# LM61495Q3_PINOUT.net
KiCad netlist of a schematic drawn in Altium Designer
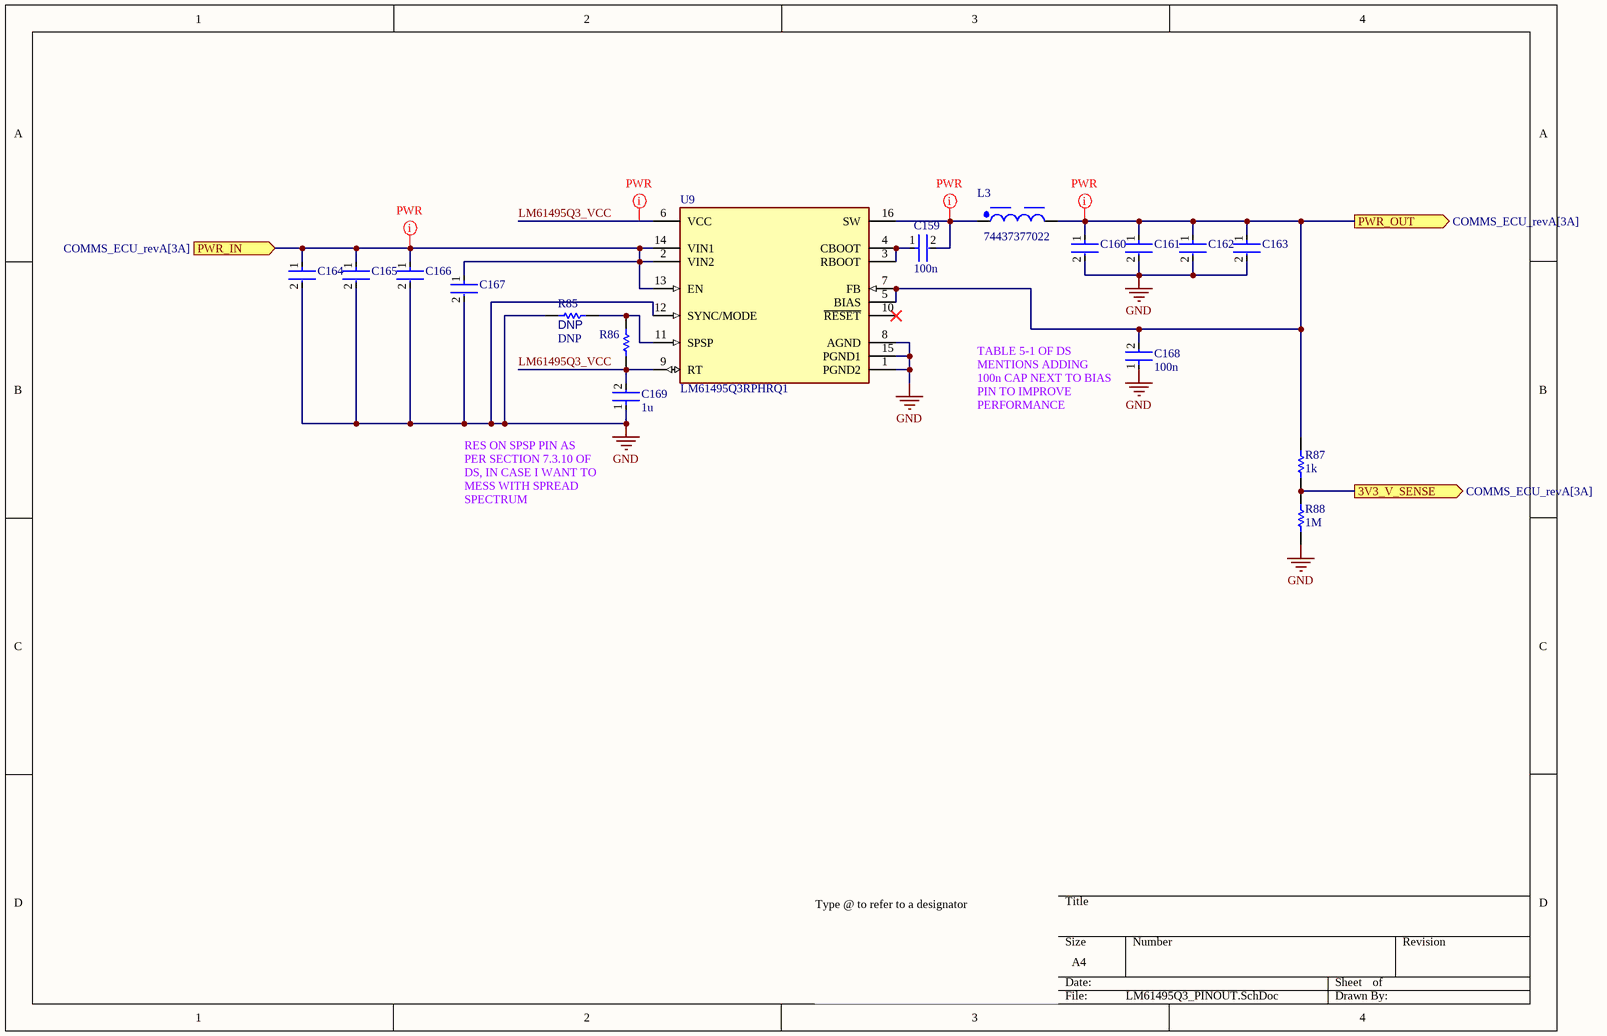
[diagram p0: LM61495Q3_PINOUT.SchDoc]

(export (version "E")
  (design (tool "Eeschema 10.0.6"))
  (components
    (comp (ref "C159")
      (value "100n")
      (footprint "FP-0402-L_1_0_0_05-W_0_5-IPC_A")
      (description "LARGE PADS, 0402 CAP, CHANGE COMMENT TO MATCH REAL P/N")
      (libsource (lib "Space Concordia") (part "b4654b650e69147ec39a6b967a45e02"))
    )
    (comp (ref "C160")
      (value "GRM32ER61C476KE15L")
      (footprint "FP-GRM32E-0_3-0_2-IPC_C")
      (description "CAP CER 47UF 16V X5R 1210")
      (fields (field (name "VOLTAGE") "16V") (field (name "TOLERANCE") "10%"))
      (libsource (lib "Altium Content Vault") (part "b4654b650e69147ec39a6b967a45e02"))
    )
    (comp (ref "C161")
      (value "GRM32ER61C476KE15L")
      (footprint "FP-GRM32E-0_3-0_2-IPC_C")
      (description "CAP CER 47UF 16V X5R 1210")
      (fields (field (name "VOLTAGE") "16V") (field (name "TOLERANCE") "10%"))
      (libsource (lib "Altium Content Vault") (part "b4654b650e69147ec39a6b967a45e02"))
    )
    (comp (ref "C162")
      (value "GRM32ER61C476KE15L")
      (footprint "FP-GRM32E-0_3-0_2-IPC_C")
      (description "CAP CER 47UF 16V X5R 1210")
      (fields (field (name "VOLTAGE") "16V") (field (name "TOLERANCE") "10%"))
      (libsource (lib "Altium Content Vault") (part "b4654b650e69147ec39a6b967a45e02"))
    )
    (comp (ref "C163")
      (value "DNP")
      (footprint "FP-GRM32E-0_3-0_2-IPC_C")
      (description "CAP CER 47UF 16V X5R 1210")
      (fields (field (name "VOLTAGE") "16V") (field (name "TOLERANCE") "10%"))
      (libsource (lib "Altium Content Vault") (part "b4654b650e69147ec39a6b967a45e02"))
    )
    (comp (ref "C164")
      (value "C3225X7R1H106M250AC")
      (footprint "FP-C3225-250-0_4-MFG")
      (description "Multilayer Ceramic Capacitors 10uF ±20% 50V X7R SMD 1210")
      (fields (field (name "TOLERANCE") "20%"))
      (libsource (lib "Altium Content Vault") (part "02cd4be3c70576c341d710602a673aa"))
    )
    (comp (ref "C165")
      (value "C3225X7R1H106M250AC")
      (footprint "FP-C3225-250-0_4-MFG")
      (description "Multilayer Ceramic Capacitors 10uF ±20% 50V X7R SMD 1210")
      (fields (field (name "TOLERANCE") "20%"))
      (libsource (lib "Altium Content Vault") (part "02cd4be3c70576c341d710602a673aa"))
    )
    (comp (ref "C166")
      (value "08055C474J4Z2A")
      (footprint "FP-0805-L_2_01_0_2-W_1_25-IPC_B")
      (description "Automotive Ceramic Capacitor, 0805, 470nF, 5%, X7R, 15%, 50V")
      (fields (field (name "TOLERANCE") "5%"))
      (libsource (lib "Altium Content Vault") (part "b4654b650e69147ec39a6b967a45e02"))
    )
    (comp (ref "C167")
      (value "08055C474J4Z2A")
      (footprint "FP-0805-L_2_01_0_2-W_1_25-IPC_B")
      (description "Automotive Ceramic Capacitor, 0805, 470nF, 5%, X7R, 15%, 50V")
      (fields (field (name "TOLERANCE") "5%"))
      (libsource (lib "Altium Content Vault") (part "b4654b650e69147ec39a6b967a45e02"))
    )
    (comp (ref "C168")
      (value "100n")
      (footprint "FP-0402-L_1_0_0_05-W_0_5-IPC_A")
      (description "LARGE PADS, 0402 CAP, CHANGE COMMENT TO MATCH REAL P/N")
      (libsource (lib "Space Concordia") (part "b4654b650e69147ec39a6b967a45e02"))
    )
    (comp (ref "C169")
      (value "1u")
      (footprint "FP-0402-L_1_0_0_05-W_0_5-IPC_A")
      (description "LARGE PADS, 0402 CAP, CHANGE COMMENT TO MATCH REAL P/N")
      (libsource (lib "Space Concordia") (part "b4654b650e69147ec39a6b967a45e02"))
    )
    (comp (ref "L3")
      (value "74437377022")
      (footprint "WE-LHMI_1335")
      (fields (field (name "TOLERANCE") "20%"))
      (libsource (lib "Altium Content Vault") (part "Inductor - 2"))
    )
    (comp (ref "R85")
      (value "DNP")
      (footprint "R0603B")
      (description "Resistor")
      (fields (field (name "ALTIUM_VALUE") "DNP"))
      (libsource (lib "Space Concordia") (part "Resistor"))
    )
    (comp (ref "R86")
      (value "0402 JUMPER")
      (footprint "RESC1005X40X25ML05T05")
      (description "READ THE NAME")
      (libsource (lib "Space Concordia") (part "CMP-009-00206-2"))
    )
    (comp (ref "R87")
      (value "1k")
      (footprint "R0603B")
      (description "Resistor")
      (libsource (lib "Space Concordia") (part "Resistor"))
    )
    (comp (ref "R88")
      (value "1M")
      (footprint "R0603B")
      (description "Resistor")
      (libsource (lib "Space Concordia") (part "Resistor"))
    )
    (comp (ref "U9")
      (value "LM61495Q3RPHRQ1")
      (footprint "FP-RPH0016A-MFG")
      (description "10-A AUTOMOTIVE BUCK CONVERTER O")
      (libsource (lib "Altium Content Vault") (part "be008cdd6a3ec40daeca3460eaab167"))
    )
  )
  (nets
    (net (code "1") (name "/3V3_V_SENSE") (class "Default")
      (node (ref "R87") (pin "1") (pinfunction "1_1") (pintype "passive"))
      (node (ref "R88") (pin "2") (pinfunction "2_2") (pintype "passive"))
    )
    (net (code "2") (name "/LM61495Q3_VCC") (class "Default")
      (node (ref "C169") (pin "2") (pinfunction "2_2") (pintype "passive"))
      (node (ref "R86") (pin "1") (pinfunction "1_1") (pintype "passive"))
      (node (ref "U9") (pin "6") (pinfunction "VCC_6") (pintype "power_in"))
      (node (ref "U9") (pin "9") (pinfunction "RT_9") (pintype "bidirectional"))
    )
    (net (code "3") (name "/PWR_IN") (class "Default")
      (node (ref "C164") (pin "1") (pinfunction "1_1") (pintype "passive"))
      (node (ref "C165") (pin "1") (pinfunction "1_1") (pintype "passive"))
      (node (ref "C166") (pin "1") (pinfunction "1_1") (pintype "passive"))
      (node (ref "C167") (pin "1") (pinfunction "1_1") (pintype "passive"))
      (node (ref "U9") (pin "13") (pinfunction "EN_13") (pintype "input"))
      (node (ref "U9") (pin "14") (pinfunction "VIN1_14") (pintype "power_in"))
      (node (ref "U9") (pin "2") (pinfunction "VIN2_2") (pintype "power_in"))
    )
    (net (code "4") (name "/PWR_OUT") (class "Default")
      (node (ref "C160") (pin "1") (pinfunction "1_1") (pintype "passive"))
      (node (ref "C161") (pin "1") (pinfunction "1_1") (pintype "passive"))
      (node (ref "C162") (pin "1") (pinfunction "1_1") (pintype "passive"))
      (node (ref "C163") (pin "1") (pinfunction "1_1") (pintype "passive"))
      (node (ref "C168") (pin "2") (pinfunction "2_2") (pintype "passive"))
      (node (ref "L3") (pin "2") (pinfunction "2_2") (pintype "passive"))
      (node (ref "R87") (pin "2") (pinfunction "2_2") (pintype "passive"))
      (node (ref "U9") (pin "5") (pinfunction "BIAS_5") (pintype "passive"))
      (node (ref "U9") (pin "7") (pinfunction "FB_7") (pintype "input"))
    )
    (net (code "5") (name "GND") (class "Default")
      (node (ref "C160") (pin "2") (pinfunction "2_2") (pintype "passive"))
      (node (ref "C161") (pin "2") (pinfunction "2_2") (pintype "passive"))
      (node (ref "C162") (pin "2") (pinfunction "2_2") (pintype "passive"))
      (node (ref "C163") (pin "2") (pinfunction "2_2") (pintype "passive"))
      (node (ref "C164") (pin "2") (pinfunction "2_2") (pintype "passive"))
      (node (ref "C165") (pin "2") (pinfunction "2_2") (pintype "passive"))
      (node (ref "C166") (pin "2") (pinfunction "2_2") (pintype "passive"))
      (node (ref "C167") (pin "2") (pinfunction "2_2") (pintype "passive"))
      (node (ref "C168") (pin "1") (pinfunction "1_1") (pintype "passive"))
      (node (ref "C169") (pin "1") (pinfunction "1_1") (pintype "passive"))
      (node (ref "R85") (pin "2") (pinfunction "2_2") (pintype "passive"))
      (node (ref "R88") (pin "1") (pinfunction "1_1") (pintype "passive"))
      (node (ref "U9") (pin "1") (pinfunction "PGND2_1") (pintype "power_in"))
      (node (ref "U9") (pin "12") (pinfunction "SYNC/MODE_12") (pintype "input"))
      (node (ref "U9") (pin "15") (pinfunction "PGND1_15") (pintype "power_in"))
      (node (ref "U9") (pin "8") (pinfunction "AGND_8") (pintype "power_in"))
    )
    (net (code "6") (name "Net-(U9-CBOOT)") (class "Default")
      (node (ref "C159") (pin "1") (pinfunction "1_1") (pintype "passive"))
      (node (ref "U9") (pin "3") (pinfunction "RBOOT_3") (pintype "power_in"))
      (node (ref "U9") (pin "4") (pinfunction "CBOOT_4") (pintype "power_in"))
    )
    (net (code "7") (name "Net-(U9-SPSP)") (class "Default")
      (node (ref "R85") (pin "1") (pinfunction "1_1") (pintype "passive"))
      (node (ref "R86") (pin "2") (pinfunction "2_2") (pintype "passive"))
      (node (ref "U9") (pin "11") (pinfunction "SPSP_11") (pintype "input"))
    )
    (net (code "8") (name "Net-(U9-SW)") (class "Default")
      (node (ref "C159") (pin "2") (pinfunction "2_2") (pintype "passive"))
      (node (ref "L3") (pin "1") (pinfunction "1_1") (pintype "passive"))
      (node (ref "U9") (pin "16") (pinfunction "SW_16") (pintype "power_in"))
    )
    (net (code "9") (name "unconnected-(U9-~{RESET}-Pad10)") (class "Default")
      (node (ref "U9") (pin "10") (pinfunction "~{RESET}_10") (pintype "open_collector+no_connect"))
    )
  )
)
